# R204X.net
KiCad netlist of a schematic drawn in EAGLE
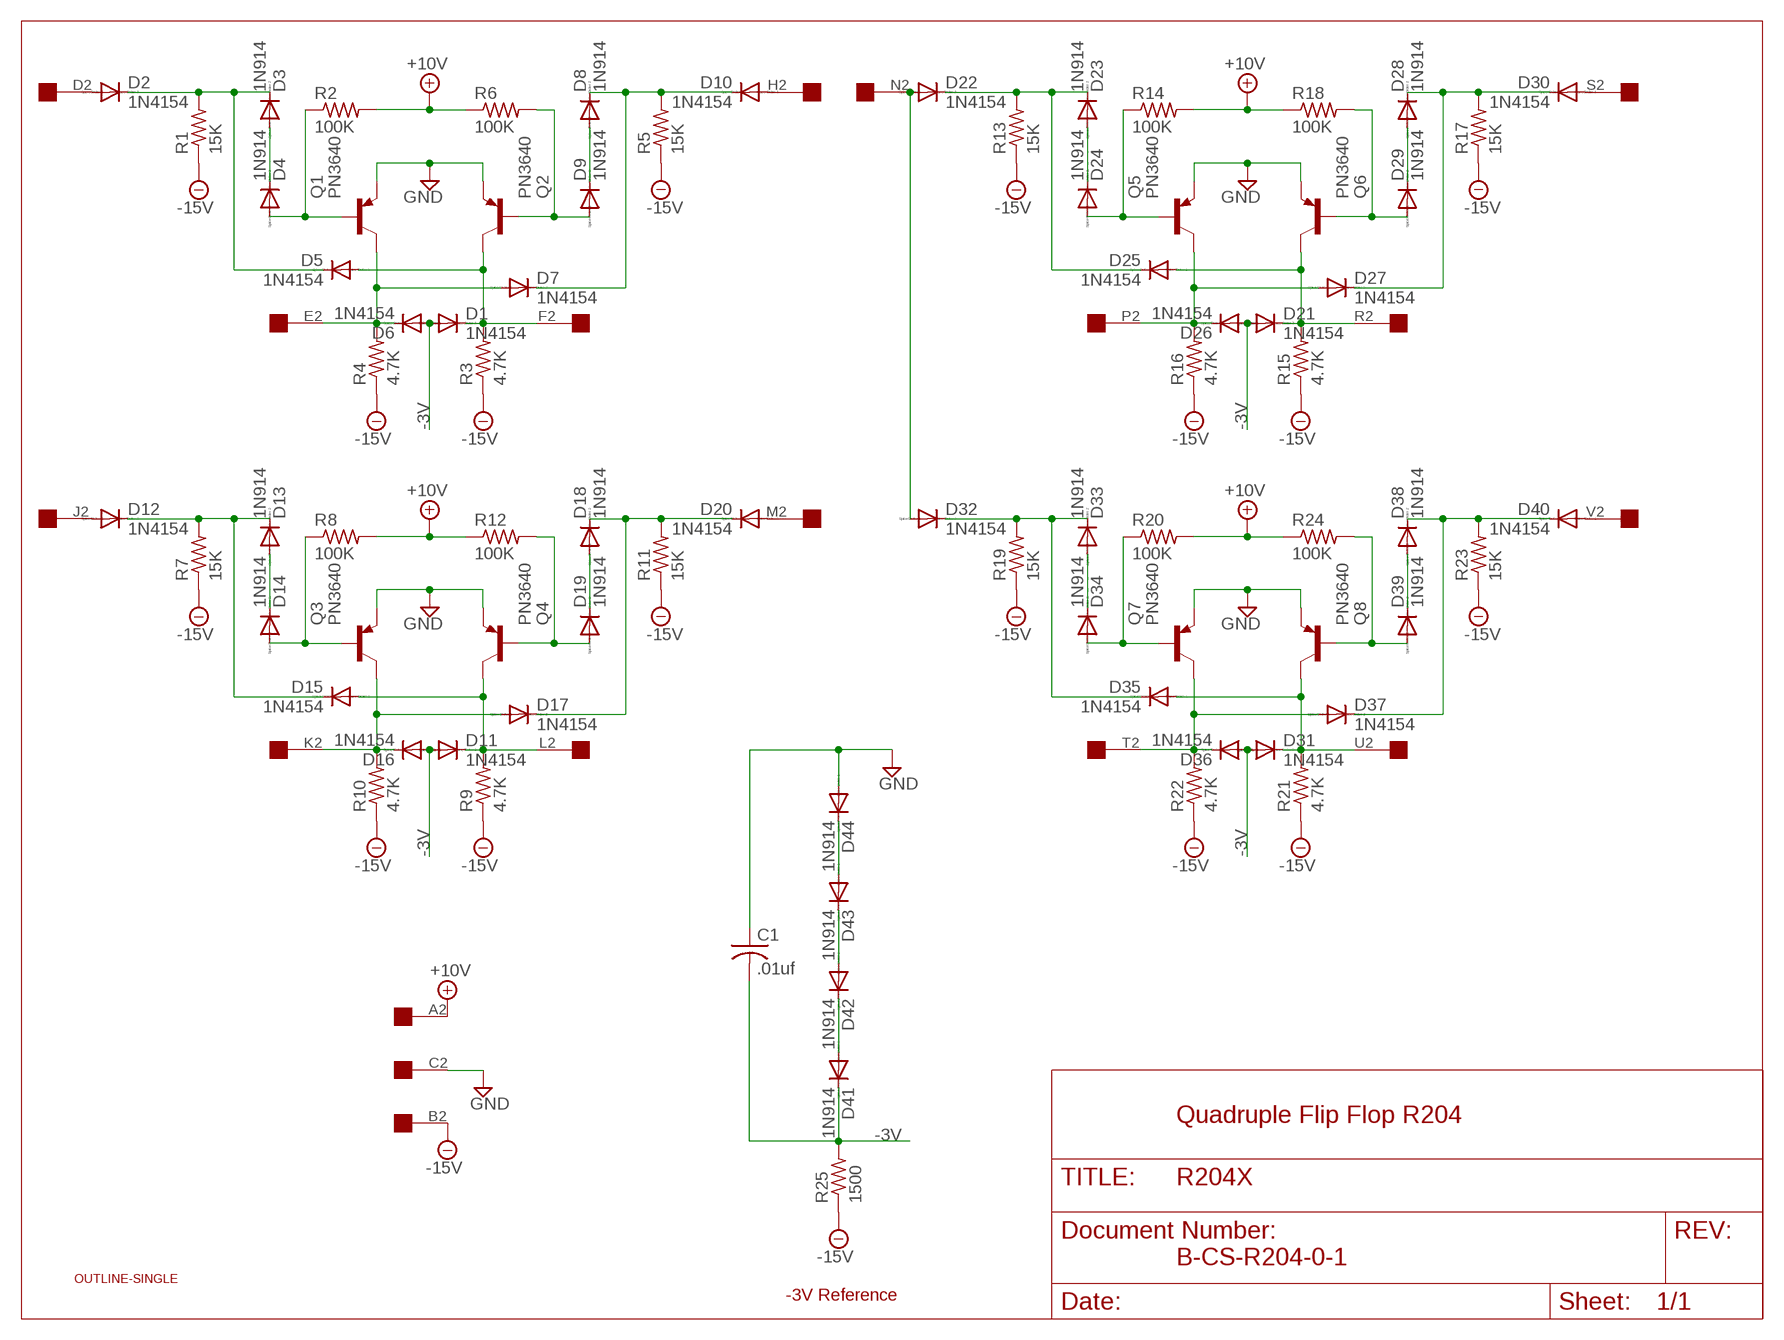
[diagram p0: schematic, sheet 1]

(export (version "E")
  (design (tool "Eeschema 10.0.6"))
  (components
    (comp (ref "C1")
      (value ".01uf")
      (footprint "eagle-import:C050-025X075")
      (libsource (lib "eagle-import") (part "C-US050-025X075"))
    )
    (comp (ref "D1")
      (value "1N4154")
      (footprint "eagle-import:DO35-10")
      (libsource (lib "eagle-import") (part "1N4148DO35-10"))
    )
    (comp (ref "D2")
      (value "1N4154")
      (footprint "eagle-import:DO35-10")
      (libsource (lib "eagle-import") (part "1N4148DO35-10"))
    )
    (comp (ref "D3")
      (value "1N914")
      (footprint "eagle-import:DO35-10")
      (libsource (lib "eagle-import") (part "1N4148DO35-10"))
    )
    (comp (ref "D4")
      (value "1N914")
      (footprint "eagle-import:DO35-10")
      (libsource (lib "eagle-import") (part "1N4148DO35-10"))
    )
    (comp (ref "D5")
      (value "1N4154")
      (footprint "eagle-import:DO35-10")
      (libsource (lib "eagle-import") (part "1N4148DO35-10"))
    )
    (comp (ref "D6")
      (value "1N4154")
      (footprint "eagle-import:DO35-10")
      (libsource (lib "eagle-import") (part "1N4148DO35-10"))
    )
    (comp (ref "D7")
      (value "1N4154")
      (footprint "eagle-import:DO35-10")
      (libsource (lib "eagle-import") (part "1N4148DO35-10"))
    )
    (comp (ref "D8")
      (value "1N914")
      (footprint "eagle-import:DO35-10")
      (libsource (lib "eagle-import") (part "1N4148DO35-10"))
    )
    (comp (ref "D9")
      (value "1N914")
      (footprint "eagle-import:DO35-10")
      (libsource (lib "eagle-import") (part "1N4148DO35-10"))
    )
    (comp (ref "D10")
      (value "1N4154")
      (footprint "eagle-import:DO35-10")
      (libsource (lib "eagle-import") (part "1N4148DO35-10"))
    )
    (comp (ref "D11")
      (value "1N4154")
      (footprint "eagle-import:DO35-10")
      (libsource (lib "eagle-import") (part "1N4148DO35-10"))
    )
    (comp (ref "D12")
      (value "1N4154")
      (footprint "eagle-import:DO35-10")
      (libsource (lib "eagle-import") (part "1N4148DO35-10"))
    )
    (comp (ref "D13")
      (value "1N914")
      (footprint "eagle-import:DO35-10")
      (libsource (lib "eagle-import") (part "1N4148DO35-10"))
    )
    (comp (ref "D14")
      (value "1N914")
      (footprint "eagle-import:DO35-10")
      (libsource (lib "eagle-import") (part "1N4148DO35-10"))
    )
    (comp (ref "D15")
      (value "1N4154")
      (footprint "eagle-import:DO35-10")
      (libsource (lib "eagle-import") (part "1N4148DO35-10"))
    )
    (comp (ref "D16")
      (value "1N4154")
      (footprint "eagle-import:DO35-10")
      (libsource (lib "eagle-import") (part "1N4148DO35-10"))
    )
    (comp (ref "D17")
      (value "1N4154")
      (footprint "eagle-import:DO35-10")
      (libsource (lib "eagle-import") (part "1N4148DO35-10"))
    )
    (comp (ref "D18")
      (value "1N914")
      (footprint "eagle-import:DO35-10")
      (libsource (lib "eagle-import") (part "1N4148DO35-10"))
    )
    (comp (ref "D19")
      (value "1N914")
      (footprint "eagle-import:DO35-10")
      (libsource (lib "eagle-import") (part "1N4148DO35-10"))
    )
    (comp (ref "D20")
      (value "1N4154")
      (footprint "eagle-import:DO35-10")
      (libsource (lib "eagle-import") (part "1N4148DO35-10"))
    )
    (comp (ref "D21")
      (value "1N4154")
      (footprint "eagle-import:DO35-10")
      (libsource (lib "eagle-import") (part "1N4148DO35-10"))
    )
    (comp (ref "D22")
      (value "1N4154")
      (footprint "eagle-import:DO35-10")
      (libsource (lib "eagle-import") (part "1N4148DO35-10"))
    )
    (comp (ref "D23")
      (value "1N914")
      (footprint "eagle-import:DO35-10")
      (libsource (lib "eagle-import") (part "1N4148DO35-10"))
    )
    (comp (ref "D24")
      (value "1N914")
      (footprint "eagle-import:DO35-10")
      (libsource (lib "eagle-import") (part "1N4148DO35-10"))
    )
    (comp (ref "D25")
      (value "1N4154")
      (footprint "eagle-import:DO35-10")
      (libsource (lib "eagle-import") (part "1N4148DO35-10"))
    )
    (comp (ref "D26")
      (value "1N4154")
      (footprint "eagle-import:DO35-10")
      (libsource (lib "eagle-import") (part "1N4148DO35-10"))
    )
    (comp (ref "D27")
      (value "1N4154")
      (footprint "eagle-import:DO35-10")
      (libsource (lib "eagle-import") (part "1N4148DO35-10"))
    )
    (comp (ref "D28")
      (value "1N914")
      (footprint "eagle-import:DO35-10")
      (libsource (lib "eagle-import") (part "1N4148DO35-10"))
    )
    (comp (ref "D29")
      (value "1N914")
      (footprint "eagle-import:DO35-10")
      (libsource (lib "eagle-import") (part "1N4148DO35-10"))
    )
    (comp (ref "D30")
      (value "1N4154")
      (footprint "eagle-import:DO35-10")
      (libsource (lib "eagle-import") (part "1N4148DO35-10"))
    )
    (comp (ref "D31")
      (value "1N4154")
      (footprint "eagle-import:DO35-10")
      (libsource (lib "eagle-import") (part "1N4148DO35-10"))
    )
    (comp (ref "D32")
      (value "1N4154")
      (footprint "eagle-import:DO35-10")
      (libsource (lib "eagle-import") (part "1N4148DO35-10"))
    )
    (comp (ref "D33")
      (value "1N914")
      (footprint "eagle-import:DO35-10")
      (libsource (lib "eagle-import") (part "1N4148DO35-10"))
    )
    (comp (ref "D34")
      (value "1N914")
      (footprint "eagle-import:DO35-10")
      (libsource (lib "eagle-import") (part "1N4148DO35-10"))
    )
    (comp (ref "D35")
      (value "1N4154")
      (footprint "eagle-import:DO35-10")
      (libsource (lib "eagle-import") (part "1N4148DO35-10"))
    )
    (comp (ref "D36")
      (value "1N4154")
      (footprint "eagle-import:DO35-10")
      (libsource (lib "eagle-import") (part "1N4148DO35-10"))
    )
    (comp (ref "D37")
      (value "1N4154")
      (footprint "eagle-import:DO35-10")
      (libsource (lib "eagle-import") (part "1N4148DO35-10"))
    )
    (comp (ref "D38")
      (value "1N914")
      (footprint "eagle-import:DO35-10")
      (libsource (lib "eagle-import") (part "1N4148DO35-10"))
    )
    (comp (ref "D39")
      (value "1N914")
      (footprint "eagle-import:DO35-10")
      (libsource (lib "eagle-import") (part "1N4148DO35-10"))
    )
    (comp (ref "D40")
      (value "1N4154")
      (footprint "eagle-import:DO35-10")
      (libsource (lib "eagle-import") (part "1N4148DO35-10"))
    )
    (comp (ref "D41")
      (value "1N914")
      (footprint "eagle-import:DO35-10")
      (libsource (lib "eagle-import") (part "1N4148DO35-10"))
    )
    (comp (ref "D42")
      (value "1N914")
      (footprint "eagle-import:DO35-10")
      (libsource (lib "eagle-import") (part "1N4148DO35-10"))
    )
    (comp (ref "D43")
      (value "1N914")
      (footprint "eagle-import:DO35-10")
      (libsource (lib "eagle-import") (part "1N4148DO35-10"))
    )
    (comp (ref "D44")
      (value "1N914")
      (footprint "eagle-import:DO35-10")
      (libsource (lib "eagle-import") (part "1N4148DO35-10"))
    )
    (comp (ref "Q1")
      (value "PN3640")
      (footprint "eagle-import:TO39")
      (libsource (lib "eagle-import") (part "2N3637"))
    )
    (comp (ref "Q2")
      (value "PN3640")
      (footprint "eagle-import:TO39")
      (libsource (lib "eagle-import") (part "2N3637"))
    )
    (comp (ref "Q3")
      (value "PN3640")
      (footprint "eagle-import:TO39")
      (libsource (lib "eagle-import") (part "2N3637"))
    )
    (comp (ref "Q4")
      (value "PN3640")
      (footprint "eagle-import:TO39")
      (libsource (lib "eagle-import") (part "2N3637"))
    )
    (comp (ref "Q5")
      (value "PN3640")
      (footprint "eagle-import:TO39")
      (libsource (lib "eagle-import") (part "2N3637"))
    )
    (comp (ref "Q6")
      (value "PN3640")
      (footprint "eagle-import:TO39")
      (libsource (lib "eagle-import") (part "2N3637"))
    )
    (comp (ref "Q7")
      (value "PN3640")
      (footprint "eagle-import:TO39")
      (libsource (lib "eagle-import") (part "2N3637"))
    )
    (comp (ref "Q8")
      (value "PN3640")
      (footprint "eagle-import:TO39")
      (libsource (lib "eagle-import") (part "2N3637"))
    )
    (comp (ref "R1")
      (value "15K")
      (footprint "eagle-import:0207_10")
      (libsource (lib "eagle-import") (part "R-US_0207/10"))
    )
    (comp (ref "R2")
      (value "100K")
      (footprint "eagle-import:0207_10")
      (libsource (lib "eagle-import") (part "R-US_0207/10"))
    )
    (comp (ref "R3")
      (value "4.7K")
      (footprint "eagle-import:0207_10")
      (libsource (lib "eagle-import") (part "R-US_0207/10"))
    )
    (comp (ref "R4")
      (value "4.7K")
      (footprint "eagle-import:0207_10")
      (libsource (lib "eagle-import") (part "R-US_0207/10"))
    )
    (comp (ref "R5")
      (value "15K")
      (footprint "eagle-import:0207_10")
      (libsource (lib "eagle-import") (part "R-US_0207/10"))
    )
    (comp (ref "R6")
      (value "100K")
      (footprint "eagle-import:0207_10")
      (libsource (lib "eagle-import") (part "R-US_0207/10"))
    )
    (comp (ref "R7")
      (value "15K")
      (footprint "eagle-import:0207_10")
      (libsource (lib "eagle-import") (part "R-US_0207/10"))
    )
    (comp (ref "R8")
      (value "100K")
      (footprint "eagle-import:0207_10")
      (libsource (lib "eagle-import") (part "R-US_0207/10"))
    )
    (comp (ref "R9")
      (value "4.7K")
      (footprint "eagle-import:0207_10")
      (libsource (lib "eagle-import") (part "R-US_0207/10"))
    )
    (comp (ref "R10")
      (value "4.7K")
      (footprint "eagle-import:0207_10")
      (libsource (lib "eagle-import") (part "R-US_0207/10"))
    )
    (comp (ref "R11")
      (value "15K")
      (footprint "eagle-import:0207_10")
      (libsource (lib "eagle-import") (part "R-US_0207/10"))
    )
    (comp (ref "R12")
      (value "100K")
      (footprint "eagle-import:0207_10")
      (libsource (lib "eagle-import") (part "R-US_0207/10"))
    )
    (comp (ref "R13")
      (value "15K")
      (footprint "eagle-import:0207_10")
      (libsource (lib "eagle-import") (part "R-US_0207/10"))
    )
    (comp (ref "R14")
      (value "100K")
      (footprint "eagle-import:0207_10")
      (libsource (lib "eagle-import") (part "R-US_0207/10"))
    )
    (comp (ref "R15")
      (value "4.7K")
      (footprint "eagle-import:0207_10")
      (libsource (lib "eagle-import") (part "R-US_0207/10"))
    )
    (comp (ref "R16")
      (value "4.7K")
      (footprint "eagle-import:0207_10")
      (libsource (lib "eagle-import") (part "R-US_0207/10"))
    )
    (comp (ref "R17")
      (value "15K")
      (footprint "eagle-import:0207_10")
      (libsource (lib "eagle-import") (part "R-US_0207/10"))
    )
    (comp (ref "R18")
      (value "100K")
      (footprint "eagle-import:0207_10")
      (libsource (lib "eagle-import") (part "R-US_0207/10"))
    )
    (comp (ref "R19")
      (value "15K")
      (footprint "eagle-import:0207_10")
      (libsource (lib "eagle-import") (part "R-US_0207/10"))
    )
    (comp (ref "R20")
      (value "100K")
      (footprint "eagle-import:0207_10")
      (libsource (lib "eagle-import") (part "R-US_0207/10"))
    )
    (comp (ref "R21")
      (value "4.7K")
      (footprint "eagle-import:0207_10")
      (libsource (lib "eagle-import") (part "R-US_0207/10"))
    )
    (comp (ref "R22")
      (value "4.7K")
      (footprint "eagle-import:0207_10")
      (libsource (lib "eagle-import") (part "R-US_0207/10"))
    )
    (comp (ref "R23")
      (value "15K")
      (footprint "eagle-import:0207_10")
      (libsource (lib "eagle-import") (part "R-US_0207/10"))
    )
    (comp (ref "R24")
      (value "100K")
      (footprint "eagle-import:0207_10")
      (libsource (lib "eagle-import") (part "R-US_0207/10"))
    )
    (comp (ref "R25")
      (value "1500")
      (footprint "eagle-import:0207_10")
      (libsource (lib "eagle-import") (part "R-US_0207/10"))
    )
    (comp (ref "U$1")
      (value "OUTLINE-SINGLE")
      (footprint "eagle-import:SINGLE")
      (libsource (lib "eagle-import") (part "OUTLINE-SINGLE"))
    )
    (comp (ref "U$2")
      (value "EDGE-1")
      (footprint "eagle-import:EDGE-CON1")
      (libsource (lib "eagle-import") (part "EDGE-1"))
    )
  )
  (nets
    (net (code "1") (name "+10V") (class "Default")
      (node (ref "R12") (pin "1") (pinfunction "1_1") (pintype "passive"))
      (node (ref "R14") (pin "2") (pinfunction "2_2") (pintype "passive"))
      (node (ref "R18") (pin "1") (pinfunction "1_1") (pintype "passive"))
      (node (ref "R2") (pin "2") (pinfunction "2_2") (pintype "passive"))
      (node (ref "R20") (pin "2") (pinfunction "2_2") (pintype "passive"))
      (node (ref "R24") (pin "1") (pinfunction "1_1") (pintype "passive"))
      (node (ref "R6") (pin "1") (pinfunction "1_1") (pintype "passive"))
      (node (ref "R8") (pin "2") (pinfunction "2_2") (pintype "passive"))
      (node (ref "U$2") (pin "A2") (pinfunction "1_A2") (pintype "bidirectional"))
    )
    (net (code "2") (name "-15V") (class "Default")
      (node (ref "R1") (pin "1") (pinfunction "1_1") (pintype "passive"))
      (node (ref "R10") (pin "1") (pinfunction "1_1") (pintype "passive"))
      (node (ref "R11") (pin "1") (pinfunction "1_1") (pintype "passive"))
      (node (ref "R13") (pin "1") (pinfunction "1_1") (pintype "passive"))
      (node (ref "R15") (pin "1") (pinfunction "1_1") (pintype "passive"))
      (node (ref "R16") (pin "1") (pinfunction "1_1") (pintype "passive"))
      (node (ref "R17") (pin "1") (pinfunction "1_1") (pintype "passive"))
      (node (ref "R19") (pin "1") (pinfunction "1_1") (pintype "passive"))
      (node (ref "R21") (pin "1") (pinfunction "1_1") (pintype "passive"))
      (node (ref "R22") (pin "1") (pinfunction "1_1") (pintype "passive"))
      (node (ref "R23") (pin "1") (pinfunction "1_1") (pintype "passive"))
      (node (ref "R25") (pin "1") (pinfunction "1_1") (pintype "passive"))
      (node (ref "R3") (pin "1") (pinfunction "1_1") (pintype "passive"))
      (node (ref "R4") (pin "1") (pinfunction "1_1") (pintype "passive"))
      (node (ref "R5") (pin "1") (pinfunction "1_1") (pintype "passive"))
      (node (ref "R7") (pin "1") (pinfunction "1_1") (pintype "passive"))
      (node (ref "R9") (pin "1") (pinfunction "1_1") (pintype "passive"))
      (node (ref "U$2") (pin "B2") (pinfunction "1_B2") (pintype "bidirectional"))
    )
    (net (code "3") (name "/-3V") (class "Default")
      (node (ref "C1") (pin "2") (pinfunction "2_2") (pintype "passive"))
      (node (ref "D1") (pin "A") (pinfunction "A_A") (pintype "passive"))
      (node (ref "D11") (pin "A") (pinfunction "A_A") (pintype "passive"))
      (node (ref "D16") (pin "A") (pinfunction "A_A") (pintype "passive"))
      (node (ref "D21") (pin "A") (pinfunction "A_A") (pintype "passive"))
      (node (ref "D26") (pin "A") (pinfunction "A_A") (pintype "passive"))
      (node (ref "D31") (pin "A") (pinfunction "A_A") (pintype "passive"))
      (node (ref "D36") (pin "A") (pinfunction "A_A") (pintype "passive"))
      (node (ref "D41") (pin "C") (pinfunction "C_C") (pintype "passive"))
      (node (ref "D6") (pin "A") (pinfunction "A_A") (pintype "passive"))
      (node (ref "R25") (pin "2") (pinfunction "2_2") (pintype "passive"))
    )
    (net (code "4") (name "GND") (class "Default")
      (node (ref "C1") (pin "1") (pinfunction "1_1") (pintype "passive"))
      (node (ref "D44") (pin "A") (pinfunction "A_A") (pintype "passive"))
      (node (ref "Q1") (pin "1") (pinfunction "E_1") (pintype "passive"))
      (node (ref "Q2") (pin "1") (pinfunction "E_1") (pintype "passive"))
      (node (ref "Q3") (pin "1") (pinfunction "E_1") (pintype "passive"))
      (node (ref "Q4") (pin "1") (pinfunction "E_1") (pintype "passive"))
      (node (ref "Q5") (pin "1") (pinfunction "E_1") (pintype "passive"))
      (node (ref "Q6") (pin "1") (pinfunction "E_1") (pintype "passive"))
      (node (ref "Q7") (pin "1") (pinfunction "E_1") (pintype "passive"))
      (node (ref "Q8") (pin "1") (pinfunction "E_1") (pintype "passive"))
      (node (ref "U$2") (pin "C2") (pinfunction "1_C2") (pintype "bidirectional"))
    )
    (net (code "5") (name "Net-(D2-PadC)") (class "Default")
      (node (ref "D2") (pin "C") (pinfunction "C_C") (pintype "passive"))
      (node (ref "D3") (pin "C") (pinfunction "C_C") (pintype "passive"))
      (node (ref "D5") (pin "C") (pinfunction "C_C") (pintype "passive"))
      (node (ref "R1") (pin "2") (pinfunction "2_2") (pintype "passive"))
    )
    (net (code "6") (name "Net-(D3-PadA)") (class "Default")
      (node (ref "D3") (pin "A") (pinfunction "A_A") (pintype "passive"))
      (node (ref "D4") (pin "C") (pinfunction "C_C") (pintype "passive"))
    )
    (net (code "7") (name "Net-(D8-PadA)") (class "Default")
      (node (ref "D8") (pin "A") (pinfunction "A_A") (pintype "passive"))
      (node (ref "D9") (pin "C") (pinfunction "C_C") (pintype "passive"))
    )
    (net (code "8") (name "Net-(D10-PadC)") (class "Default")
      (node (ref "D10") (pin "C") (pinfunction "C_C") (pintype "passive"))
      (node (ref "D7") (pin "C") (pinfunction "C_C") (pintype "passive"))
      (node (ref "D8") (pin "C") (pinfunction "C_C") (pintype "passive"))
      (node (ref "R5") (pin "2") (pinfunction "2_2") (pintype "passive"))
    )
    (net (code "9") (name "Net-(D12-PadC)") (class "Default")
      (node (ref "D12") (pin "C") (pinfunction "C_C") (pintype "passive"))
      (node (ref "D13") (pin "C") (pinfunction "C_C") (pintype "passive"))
      (node (ref "D15") (pin "C") (pinfunction "C_C") (pintype "passive"))
      (node (ref "R7") (pin "2") (pinfunction "2_2") (pintype "passive"))
    )
    (net (code "10") (name "Net-(D13-PadA)") (class "Default")
      (node (ref "D13") (pin "A") (pinfunction "A_A") (pintype "passive"))
      (node (ref "D14") (pin "C") (pinfunction "C_C") (pintype "passive"))
    )
    (net (code "11") (name "Net-(D17-PadC)") (class "Default")
      (node (ref "D17") (pin "C") (pinfunction "C_C") (pintype "passive"))
      (node (ref "D18") (pin "C") (pinfunction "C_C") (pintype "passive"))
      (node (ref "D20") (pin "C") (pinfunction "C_C") (pintype "passive"))
      (node (ref "R11") (pin "2") (pinfunction "2_2") (pintype "passive"))
    )
    (net (code "12") (name "Net-(D18-PadA)") (class "Default")
      (node (ref "D18") (pin "A") (pinfunction "A_A") (pintype "passive"))
      (node (ref "D19") (pin "C") (pinfunction "C_C") (pintype "passive"))
    )
    (net (code "13") (name "Net-(D22-PadC)") (class "Default")
      (node (ref "D22") (pin "C") (pinfunction "C_C") (pintype "passive"))
      (node (ref "D23") (pin "C") (pinfunction "C_C") (pintype "passive"))
      (node (ref "D25") (pin "C") (pinfunction "C_C") (pintype "passive"))
      (node (ref "R13") (pin "2") (pinfunction "2_2") (pintype "passive"))
    )
    (net (code "14") (name "Net-(D23-PadA)") (class "Default")
      (node (ref "D23") (pin "A") (pinfunction "A_A") (pintype "passive"))
      (node (ref "D24") (pin "C") (pinfunction "C_C") (pintype "passive"))
    )
    (net (code "15") (name "Net-(D27-PadC)") (class "Default")
      (node (ref "D27") (pin "C") (pinfunction "C_C") (pintype "passive"))
      (node (ref "D28") (pin "C") (pinfunction "C_C") (pintype "passive"))
      (node (ref "D30") (pin "C") (pinfunction "C_C") (pintype "passive"))
      (node (ref "R17") (pin "2") (pinfunction "2_2") (pintype "passive"))
    )
    (net (code "16") (name "Net-(D28-PadA)") (class "Default")
      (node (ref "D28") (pin "A") (pinfunction "A_A") (pintype "passive"))
      (node (ref "D29") (pin "C") (pinfunction "C_C") (pintype "passive"))
    )
    (net (code "17") (name "Net-(D32-PadC)") (class "Default")
      (node (ref "D32") (pin "C") (pinfunction "C_C") (pintype "passive"))
      (node (ref "D33") (pin "C") (pinfunction "C_C") (pintype "passive"))
      (node (ref "D35") (pin "C") (pinfunction "C_C") (pintype "passive"))
      (node (ref "R19") (pin "2") (pinfunction "2_2") (pintype "passive"))
    )
    (net (code "18") (name "Net-(D33-PadA)") (class "Default")
      (node (ref "D33") (pin "A") (pinfunction "A_A") (pintype "passive"))
      (node (ref "D34") (pin "C") (pinfunction "C_C") (pintype "passive"))
    )
    (net (code "19") (name "Net-(D37-PadC)") (class "Default")
      (node (ref "D37") (pin "C") (pinfunction "C_C") (pintype "passive"))
      (node (ref "D38") (pin "C") (pinfunction "C_C") (pintype "passive"))
      (node (ref "D40") (pin "C") (pinfunction "C_C") (pintype "passive"))
      (node (ref "R23") (pin "2") (pinfunction "2_2") (pintype "passive"))
    )
    (net (code "20") (name "Net-(D38-PadA)") (class "Default")
      (node (ref "D38") (pin "A") (pinfunction "A_A") (pintype "passive"))
      (node (ref "D39") (pin "C") (pinfunction "C_C") (pintype "passive"))
    )
    (net (code "21") (name "Net-(D41-PadA)") (class "Default")
      (node (ref "D41") (pin "A") (pinfunction "A_A") (pintype "passive"))
      (node (ref "D42") (pin "C") (pinfunction "C_C") (pintype "passive"))
    )
    (net (code "22") (name "Net-(D42-PadA)") (class "Default")
      (node (ref "D42") (pin "A") (pinfunction "A_A") (pintype "passive"))
      (node (ref "D43") (pin "C") (pinfunction "C_C") (pintype "passive"))
    )
    (net (code "23") (name "Net-(D43-PadA)") (class "Default")
      (node (ref "D43") (pin "A") (pinfunction "A_A") (pintype "passive"))
      (node (ref "D44") (pin "C") (pinfunction "C_C") (pintype "passive"))
    )
    (net (code "24") (name "Net-(Q1-B)") (class "Default")
      (node (ref "D4") (pin "A") (pinfunction "A_A") (pintype "passive"))
      (node (ref "Q1") (pin "2") (pinfunction "B_2") (pintype "passive"))
      (node (ref "R2") (pin "1") (pinfunction "1_1") (pintype "passive"))
    )
    (net (code "25") (name "Net-(Q1-C)") (class "Default")
      (node (ref "D6") (pin "C") (pinfunction "C_C") (pintype "passive"))
      (node (ref "D7") (pin "A") (pinfunction "A_A") (pintype "passive"))
      (node (ref "Q1") (pin "3") (pinfunction "C_3") (pintype "passive"))
      (node (ref "R4") (pin "2") (pinfunction "2_2") (pintype "passive"))
      (node (ref "U$2") (pin "E2") (pinfunction "1_E2") (pintype "bidirectional"))
    )
    (net (code "26") (name "Net-(Q2-B)") (class "Default")
      (node (ref "D9") (pin "A") (pinfunction "A_A") (pintype "passive"))
      (node (ref "Q2") (pin "2") (pinfunction "B_2") (pintype "passive"))
      (node (ref "R6") (pin "2") (pinfunction "2_2") (pintype "passive"))
    )
    (net (code "27") (name "Net-(Q2-C)") (class "Default")
      (node (ref "D1") (pin "C") (pinfunction "C_C") (pintype "passive"))
      (node (ref "D5") (pin "A") (pinfunction "A_A") (pintype "passive"))
      (node (ref "Q2") (pin "3") (pinfunction "C_3") (pintype "passive"))
      (node (ref "R3") (pin "2") (pinfunction "2_2") (pintype "passive"))
      (node (ref "U$2") (pin "F2") (pinfunction "1_F2") (pintype "bidirectional"))
    )
    (net (code "28") (name "Net-(Q3-B)") (class "Default")
      (node (ref "D14") (pin "A") (pinfunction "A_A") (pintype "passive"))
      (node (ref "Q3") (pin "2") (pinfunction "B_2") (pintype "passive"))
      (node (ref "R8") (pin "1") (pinfunction "1_1") (pintype "passive"))
    )
    (net (code "29") (name "Net-(Q3-C)") (class "Default")
      (node (ref "D16") (pin "C") (pinfunction "C_C") (pintype "passive"))
      (node (ref "D17") (pin "A") (pinfunction "A_A") (pintype "passive"))
      (node (ref "Q3") (pin "3") (pinfunction "C_3") (pintype "passive"))
      (node (ref "R10") (pin "2") (pinfunction "2_2") (pintype "passive"))
      (node (ref "U$2") (pin "K2") (pinfunction "1_K2") (pintype "bidirectional"))
    )
    (net (code "30") (name "Net-(Q4-B)") (class "Default")
      (node (ref "D19") (pin "A") (pinfunction "A_A") (pintype "passive"))
      (node (ref "Q4") (pin "2") (pinfunction "B_2") (pintype "passive"))
      (node (ref "R12") (pin "2") (pinfunction "2_2") (pintype "passive"))
    )
    (net (code "31") (name "Net-(Q4-C)") (class "Default")
      (node (ref "D11") (pin "C") (pinfunction "C_C") (pintype "passive"))
      (node (ref "D15") (pin "A") (pinfunction "A_A") (pintype "passive"))
      (node (ref "Q4") (pin "3") (pinfunction "C_3") (pintype "passive"))
      (node (ref "R9") (pin "2") (pinfunction "2_2") (pintype "passive"))
      (node (ref "U$2") (pin "L2") (pinfunction "1_L2") (pintype "bidirectional"))
    )
    (net (code "32") (name "Net-(Q5-B)") (class "Default")
      (node (ref "D24") (pin "A") (pinfunction "A_A") (pintype "passive"))
      (node (ref "Q5") (pin "2") (pinfunction "B_2") (pintype "passive"))
      (node (ref "R14") (pin "1") (pinfunction "1_1") (pintype "passive"))
    )
    (net (code "33") (name "Net-(Q5-C)") (class "Default")
      (node (ref "D26") (pin "C") (pinfunction "C_C") (pintype "passive"))
      (node (ref "D27") (pin "A") (pinfunction "A_A") (pintype "passive"))
      (node (ref "Q5") (pin "3") (pinfunction "C_3") (pintype "passive"))
      (node (ref "R16") (pin "2") (pinfunction "2_2") (pintype "passive"))
      (node (ref "U$2") (pin "P2") (pinfunction "1_P2") (pintype "bidirectional"))
    )
    (net (code "34") (name "Net-(Q6-B)") (class "Default")
      (node (ref "D29") (pin "A") (pinfunction "A_A") (pintype "passive"))
      (node (ref "Q6") (pin "2") (pinfunction "B_2") (pintype "passive"))
      (node (ref "R18") (pin "2") (pinfunction "2_2") (pintype "passive"))
    )
    (net (code "35") (name "Net-(Q6-C)") (class "Default")
      (node (ref "D21") (pin "C") (pinfunction "C_C") (pintype "passive"))
      (node (ref "D25") (pin "A") (pinfunction "A_A") (pintype "passive"))
      (node (ref "Q6") (pin "3") (pinfunction "C_3") (pintype "passive"))
      (node (ref "R15") (pin "2") (pinfunction "2_2") (pintype "passive"))
      (node (ref "U$2") (pin "R2") (pinfunction "1_R2") (pintype "bidirectional"))
    )
    (net (code "36") (name "Net-(Q7-B)") (class "Default")
      (node (ref "D34") (pin "A") (pinfunction "A_A") (pintype "passive"))
      (node (ref "Q7") (pin "2") (pinfunction "B_2") (pintype "passive"))
      (node (ref "R20") (pin "1") (pinfunction "1_1") (pintype "passive"))
    )
    (net (code "37") (name "Net-(Q7-C)") (class "Default")
      (node (ref "D36") (pin "C") (pinfunction "C_C") (pintype "passive"))
      (node (ref "D37") (pin "A") (pinfunction "A_A") (pintype "passive"))
      (node (ref "Q7") (pin "3") (pinfunction "C_3") (pintype "passive"))
      (node (ref "R22") (pin "2") (pinfunction "2_2") (pintype "passive"))
      (node (ref "U$2") (pin "T2") (pinfunction "1_T2") (pintype "bidirectional"))
    )
    (net (code "38") (name "Net-(Q8-B)") (class "Default")
      (node (ref "D39") (pin "A") (pinfunction "A_A") (pintype "passive"))
      (node (ref "Q8") (pin "2") (pinfunction "B_2") (pintype "passive"))
      (node (ref "R24") (pin "2") (pinfunction "2_2") (pintype "passive"))
    )
    (net (code "39") (name "Net-(Q8-C)") (class "Default")
      (node (ref "D31") (pin "C") (pinfunction "C_C") (pintype "passive"))
      (node (ref "D35") (pin "A") (pinfunction "A_A") (pintype "passive"))
      (node (ref "Q8") (pin "3") (pinfunction "C_3") (pintype "passive"))
      (node (ref "R21") (pin "2") (pinfunction "2_2") (pintype "passive"))
      (node (ref "U$2") (pin "U2") (pinfunction "1_U2") (pintype "bidirectional"))
    )
    (net (code "40") (name "Net-(U$2D-1)") (class "Default")
      (node (ref "D2") (pin "A") (pinfunction "A_A") (pintype "passive"))
      (node (ref "U$2") (pin "D2") (pinfunction "1_D2") (pintype "bidirectional"))
    )
    (net (code "41") (name "Net-(U$2G-1)") (class "Default")
      (node (ref "D10") (pin "A") (pinfunction "A_A") (pintype "passive"))
      (node (ref "U$2") (pin "H2") (pinfunction "1_H2") (pintype "bidirectional"))
    )
    (net (code "42") (name "Net-(U$2H-1)") (class "Default")
      (node (ref "D12") (pin "A") (pinfunction "A_A") (pintype "passive"))
      (node (ref "U$2") (pin "J2") (pinfunction "1_J2") (pintype "bidirectional"))
    )
    (net (code "43") (name "Net-(U$2K-1)") (class "Default")
      (node (ref "D20") (pin "A") (pinfunction "A_A") (pintype "passive"))
      (node (ref "U$2") (pin "M2") (pinfunction "1_M2") (pintype "bidirectional"))
    )
    (net (code "44") (name "Net-(U$2L-1)") (class "Default")
      (node (ref "D22") (pin "A") (pinfunction "A_A") (pintype "passive"))
      (node (ref "D32") (pin "A") (pinfunction "A_A") (pintype "passive"))
      (node (ref "U$2") (pin "N2") (pinfunction "1_N2") (pintype "bidirectional"))
    )
    (net (code "45") (name "Net-(U$2O-1)") (class "Default")
      (node (ref "D30") (pin "A") (pinfunction "A_A") (pintype "passive"))
      (node (ref "U$2") (pin "S2") (pinfunction "1_S2") (pintype "bidirectional"))
    )
    (net (code "46") (name "Net-(U$2R-1)") (class "Default")
      (node (ref "D40") (pin "A") (pinfunction "A_A") (pintype "passive"))
      (node (ref "U$2") (pin "V2") (pinfunction "1_V2") (pintype "bidirectional"))
    )
  )
)
